# ASH067476.net
KiCad netlist of a schematic drawn in Altium Designer
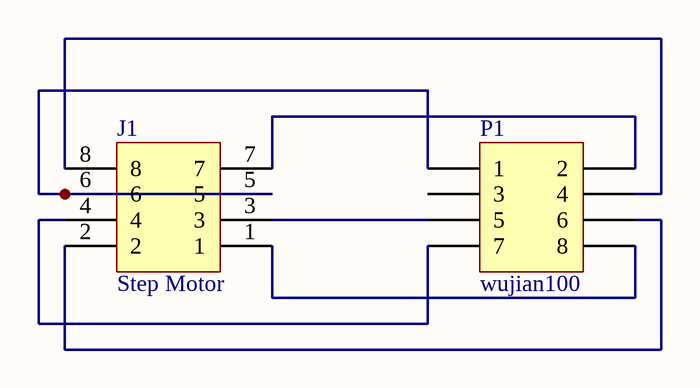
[diagram p0: ASH067476_智信同德_原理图源文件.SchDoc]

(export (version "E")
  (design (tool "Eeschema 10.0.6"))
  (components
    (comp (ref "J1")
      (value "Pin HDR2X4")
      (footprint "Pin HDR2X4/2.54mm-S")
      (libsource (lib "Per_Connector") (part "Pin HDR2X4"))
    )
    (comp (ref "P1")
      (value "MHDR2X4")
      (footprint "MHDR2X4")
      (description "Header, 4-Pin, Dual row")
      (fields (field (name "PUBLISHER") "Altium Limited"))
      (libsource (lib "Miscellaneous Connectors") (part "MHDR2X4"))
    )
  )
  (nets
    (net (code "1") (name "Net-(J1-Pad1)") (class "Default")
      (node (ref "J1") (pin "1") (pinfunction "1_1") (pintype "passive"))
      (node (ref "P1") (pin "8") (pinfunction "8_8") (pintype "passive"))
    )
    (net (code "2") (name "Net-(J1-Pad2)") (class "Default")
      (node (ref "J1") (pin "2") (pinfunction "2_2") (pintype "passive"))
      (node (ref "P1") (pin "6") (pinfunction "6_6") (pintype "passive"))
    )
    (net (code "3") (name "Net-(J1-Pad3)") (class "Default")
      (node (ref "J1") (pin "3") (pinfunction "3_3") (pintype "passive"))
      (node (ref "P1") (pin "5") (pinfunction "5_5") (pintype "passive"))
    )
    (net (code "4") (name "Net-(J1-Pad4)") (class "Default")
      (node (ref "J1") (pin "4") (pinfunction "4_4") (pintype "passive"))
      (node (ref "P1") (pin "7") (pinfunction "7_7") (pintype "passive"))
    )
    (net (code "5") (name "Net-(J1-Pad5)") (class "Default")
      (node (ref "J1") (pin "5") (pinfunction "5_5") (pintype "passive"))
      (node (ref "J1") (pin "6") (pinfunction "6_6") (pintype "passive"))
      (node (ref "P1") (pin "1") (pinfunction "1_1") (pintype "passive"))
    )
    (net (code "6") (name "Net-(J1-Pad7)") (class "Default")
      (node (ref "J1") (pin "7") (pinfunction "7_7") (pintype "passive"))
      (node (ref "P1") (pin "2") (pinfunction "2_2") (pintype "passive"))
    )
    (net (code "7") (name "Net-(J1-Pad8)") (class "Default")
      (node (ref "J1") (pin "8") (pinfunction "8_8") (pintype "passive"))
      (node (ref "P1") (pin "4") (pinfunction "4_4") (pintype "passive"))
    )
    (net (code "8") (name "unconnected-(P1-Pad3)") (class "Default")
      (node (ref "P1") (pin "3") (pinfunction "3_3") (pintype "passive"))
    )
  )
)
